# WiFi_UART_Board_R1_0.net
KiCad netlist of a schematic drawn in EAGLE
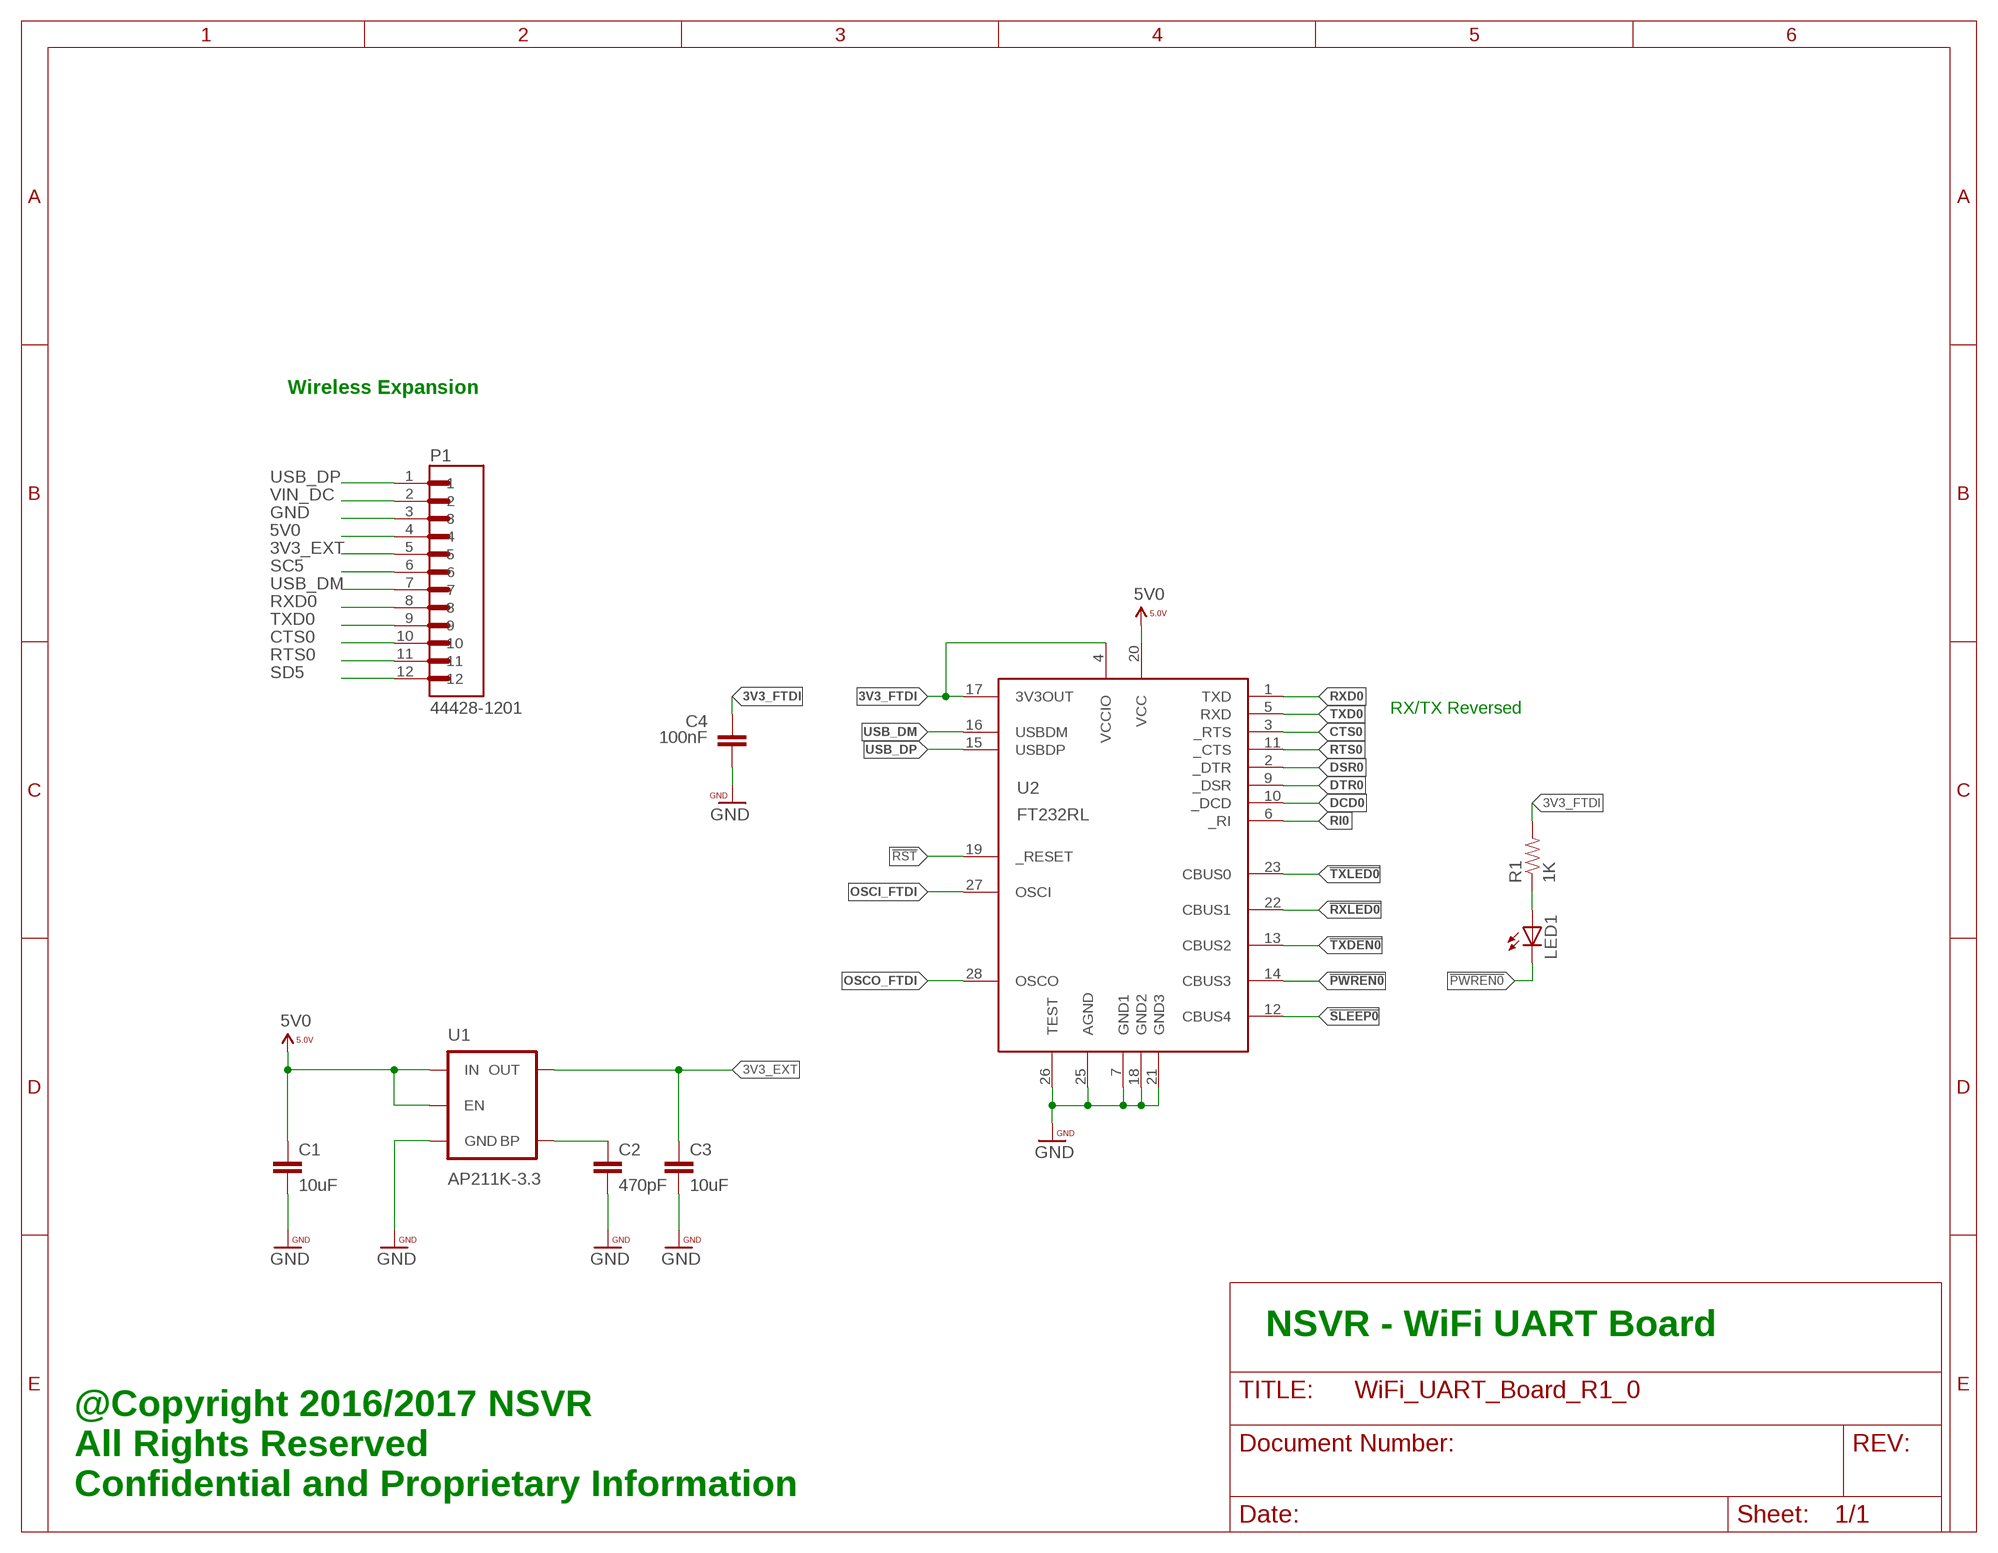
[diagram p0: schematic, sheet 1]

(export (version "E")
  (design (tool "Eeschema 10.0.6"))
  (components
    (comp (ref "C1")
      (value "10uF")
      (footprint "eagle-import:0603-CAP")
      (libsource (lib "eagle-import") (part "CAP0603-CAP"))
    )
    (comp (ref "C2")
      (value "470pF")
      (footprint "eagle-import:0402-CAP")
      (libsource (lib "eagle-import") (part "CAP0402-CAP"))
    )
    (comp (ref "C3")
      (value "10uF")
      (footprint "eagle-import:0603-CAP")
      (libsource (lib "eagle-import") (part "CAP0603-CAP"))
    )
    (comp (ref "C4")
      (value "100nF")
      (footprint "eagle-import:0402-CAP")
      (libsource (lib "eagle-import") (part "CAP0402-CAP"))
    )
    (comp (ref "LED1")
      (value "LEDCHIP-LED0603")
      (footprint "eagle-import:CHIP-LED0603")
      (libsource (lib "eagle-import") (part "LEDCHIP-LED0603"))
    )
    (comp (ref "P1")
      (value "44428-1201")
      (footprint "eagle-import:MOLEX_44428-1201")
      (fields (field (name "MF") "Molex"))
      (libsource (lib "eagle-import") (part "44428-1201"))
    )
    (comp (ref "R1")
      (value "1K")
      (footprint "eagle-import:EIA-0402")
      (libsource (lib "eagle-import") (part "RESISTOR0402-TYP"))
    )
    (comp (ref "U1")
      (value "AP211K-3.3")
      (footprint "eagle-import:SOT23-5")
      (libsource (lib "eagle-import") (part "V_REG_MIC52053.3V"))
    )
    (comp (ref "U2")
      (value "FT232RL")
      (footprint "eagle-import:SSOP28DB")
      (libsource (lib "eagle-import") (part "FT232RL"))
    )
  )
  (nets
    (net (code "1") (name "/SC5") (class "Default")
      (node (ref "P1") (pin "6") (pinfunction "6_6") (pintype "passive"))
    )
    (net (code "2") (name "/SD5") (class "Default")
      (node (ref "P1") (pin "12") (pinfunction "12_12") (pintype "passive"))
    )
    (net (code "3") (name "/VIN_DC") (class "Default")
      (node (ref "P1") (pin "2") (pinfunction "2_2") (pintype "passive"))
    )
    (net (code "4") (name "/~{PWREN0}") (class "Default")
      (node (ref "LED1") (pin "C") (pinfunction "C_C") (pintype "passive"))
      (node (ref "U2") (pin "14") (pinfunction "CBUS3_14") (pintype "bidirectional"))
    )
    (net (code "5") (name "/~{RST}") (class "Default")
      (node (ref "U2") (pin "19") (pinfunction "_RESET_19") (pintype "input"))
    )
    (net (code "6") (name "/~{RXLED0}") (class "Default")
      (node (ref "U2") (pin "22") (pinfunction "CBUS1_22") (pintype "bidirectional"))
    )
    (net (code "7") (name "/~{SLEEP0}") (class "Default")
      (node (ref "U2") (pin "12") (pinfunction "CBUS4_12") (pintype "bidirectional"))
    )
    (net (code "8") (name "/~{TXDEN0}") (class "Default")
      (node (ref "U2") (pin "13") (pinfunction "CBUS2_13") (pintype "bidirectional"))
    )
    (net (code "9") (name "/~{TXLED0}") (class "Default")
      (node (ref "U2") (pin "23") (pinfunction "CBUS0_23") (pintype "bidirectional"))
    )
    (net (code "10") (name "3V3_EXT") (class "Default")
      (node (ref "C3") (pin "1") (pinfunction "1_1") (pintype "passive"))
      (node (ref "P1") (pin "5") (pinfunction "5_5") (pintype "passive"))
      (node (ref "U1") (pin "5") (pinfunction "OUT_5") (pintype "passive"))
    )
    (net (code "11") (name "3V3_FTDI") (class "Default")
      (node (ref "C4") (pin "1") (pinfunction "1_1") (pintype "passive"))
      (node (ref "R1") (pin "2") (pinfunction "2_2") (pintype "passive"))
      (node (ref "U2") (pin "17") (pinfunction "3V3OUT_17") (pintype "output"))
      (node (ref "U2") (pin "4") (pinfunction "VCCIO_4") (pintype "power_in"))
    )
    (net (code "12") (name "5V0") (class "Default")
      (node (ref "C1") (pin "1") (pinfunction "1_1") (pintype "passive"))
      (node (ref "P1") (pin "4") (pinfunction "4_4") (pintype "passive"))
      (node (ref "U1") (pin "1") (pinfunction "IN_1") (pintype "input"))
      (node (ref "U1") (pin "3") (pinfunction "EN_3") (pintype "input"))
      (node (ref "U2") (pin "20") (pinfunction "VCC_20") (pintype "power_in"))
    )
    (net (code "13") (name "CTS0") (class "Default")
      (node (ref "P1") (pin "10") (pinfunction "10_10") (pintype "passive"))
      (node (ref "U2") (pin "3") (pinfunction "_RTS_3") (pintype "output"))
    )
    (net (code "14") (name "DCD0") (class "Default")
      (node (ref "U2") (pin "10") (pinfunction "_DCD_10") (pintype "input"))
    )
    (net (code "15") (name "DSR0") (class "Default")
      (node (ref "U2") (pin "2") (pinfunction "_DTR_2") (pintype "output"))
    )
    (net (code "16") (name "DTR0") (class "Default")
      (node (ref "U2") (pin "9") (pinfunction "_DSR_9") (pintype "input"))
    )
    (net (code "17") (name "GND") (class "Default")
      (node (ref "C1") (pin "2") (pinfunction "2_2") (pintype "passive"))
      (node (ref "C2") (pin "2") (pinfunction "2_2") (pintype "passive"))
      (node (ref "C3") (pin "2") (pinfunction "2_2") (pintype "passive"))
      (node (ref "C4") (pin "2") (pinfunction "2_2") (pintype "passive"))
      (node (ref "P1") (pin "3") (pinfunction "3_3") (pintype "passive"))
      (node (ref "U1") (pin "2") (pinfunction "GND_2") (pintype "input"))
      (node (ref "U2") (pin "18") (pinfunction "GND2_18") (pintype "power_in"))
      (node (ref "U2") (pin "21") (pinfunction "GND3_21") (pintype "power_in"))
      (node (ref "U2") (pin "25") (pinfunction "AGND_25") (pintype "power_in"))
      (node (ref "U2") (pin "26") (pinfunction "TEST_26") (pintype "input"))
      (node (ref "U2") (pin "7") (pinfunction "GND1_7") (pintype "power_in"))
    )
    (net (code "18") (name "Net-(LED1-PadA)") (class "Default")
      (node (ref "LED1") (pin "A") (pinfunction "A_A") (pintype "passive"))
      (node (ref "R1") (pin "1") (pinfunction "1_1") (pintype "passive"))
    )
    (net (code "19") (name "Net-(U1-BP)") (class "Default")
      (node (ref "C2") (pin "1") (pinfunction "1_1") (pintype "passive"))
      (node (ref "U1") (pin "4") (pinfunction "BP_4") (pintype "input"))
    )
    (net (code "20") (name "OSCI_FTDI") (class "Default")
      (node (ref "U2") (pin "27") (pinfunction "OSCI_27") (pintype "input"))
    )
    (net (code "21") (name "OSCO_FTDI") (class "Default")
      (node (ref "U2") (pin "28") (pinfunction "OSCO_28") (pintype "output"))
    )
    (net (code "22") (name "RI0") (class "Default")
      (node (ref "U2") (pin "6") (pinfunction "_RI_6") (pintype "input"))
    )
    (net (code "23") (name "RTS0") (class "Default")
      (node (ref "P1") (pin "11") (pinfunction "11_11") (pintype "passive"))
      (node (ref "U2") (pin "11") (pinfunction "_CTS_11") (pintype "input"))
    )
    (net (code "24") (name "RXD0") (class "Default")
      (node (ref "P1") (pin "8") (pinfunction "8_8") (pintype "passive"))
      (node (ref "U2") (pin "1") (pinfunction "TXD_1") (pintype "output"))
    )
    (net (code "25") (name "TXD0") (class "Default")
      (node (ref "P1") (pin "9") (pinfunction "9_9") (pintype "passive"))
      (node (ref "U2") (pin "5") (pinfunction "RXD_5") (pintype "input"))
    )
    (net (code "26") (name "USB_DM") (class "Default")
      (node (ref "P1") (pin "7") (pinfunction "7_7") (pintype "passive"))
      (node (ref "U2") (pin "16") (pinfunction "USBDM_16") (pintype "bidirectional"))
    )
    (net (code "27") (name "USB_DP") (class "Default")
      (node (ref "P1") (pin "1") (pinfunction "1_1") (pintype "passive"))
      (node (ref "U2") (pin "15") (pinfunction "USBDP_15") (pintype "bidirectional"))
    )
  )
)
